# zjb.net
KiCad netlist of a schematic drawn in Altium Designer
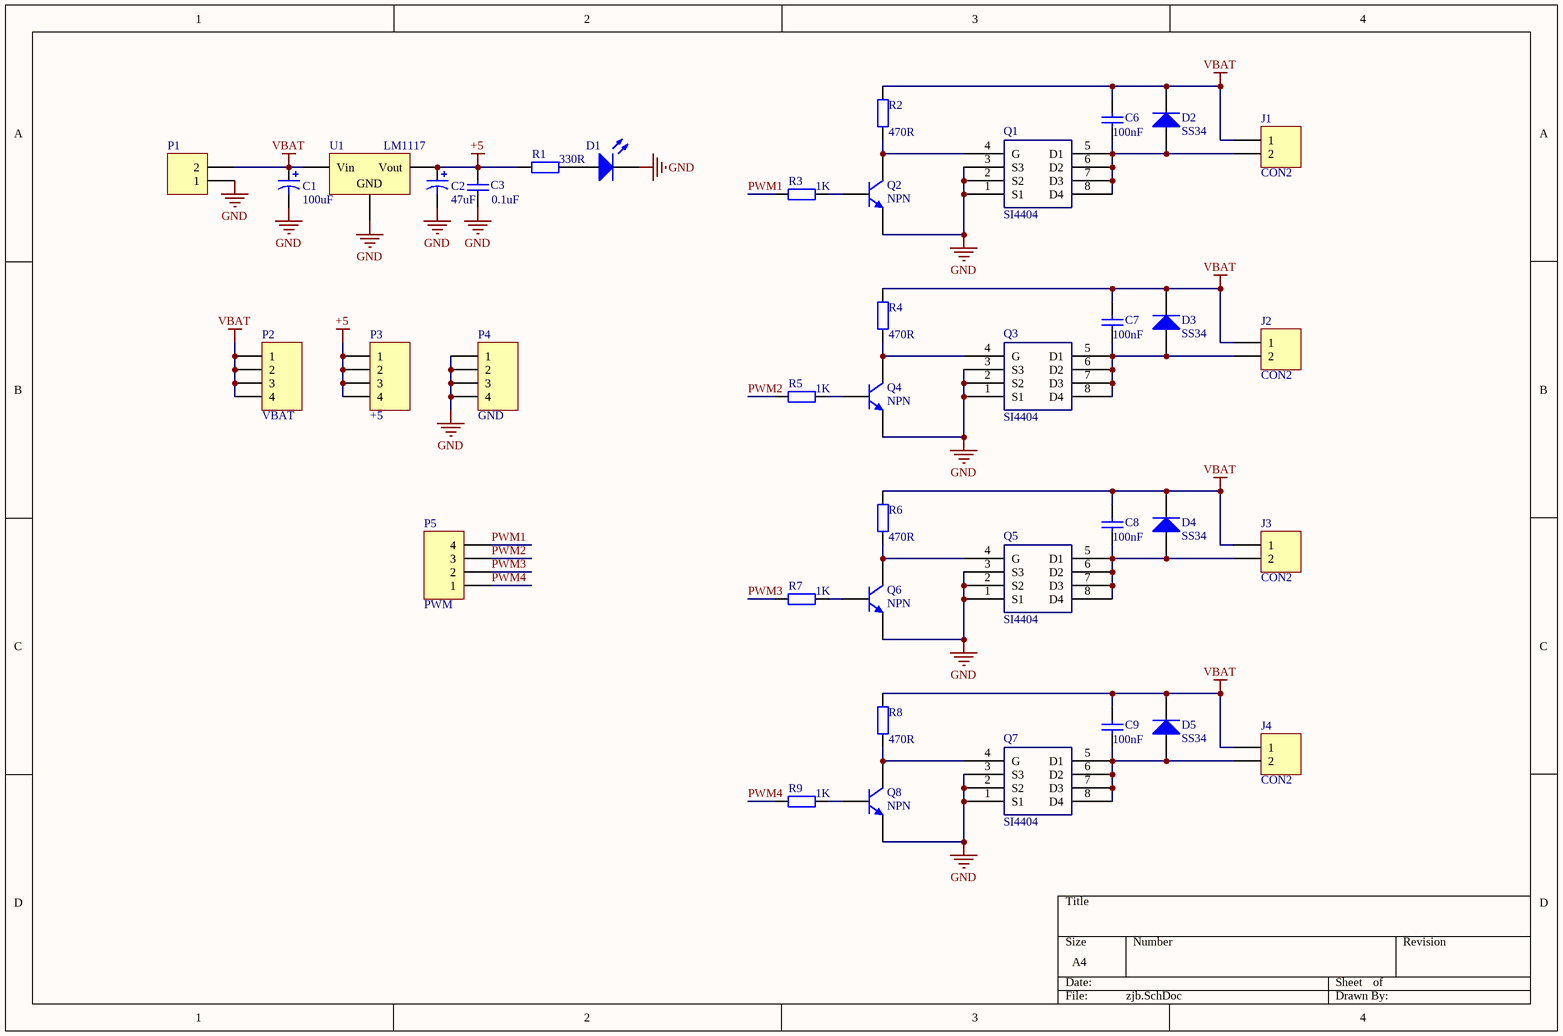
[diagram p0: zjb.SchDoc]

(export (version "E")
  (design (tool "Eeschema 10.0.6"))
  (components
    (comp (ref "C1")
      (value "100uF")
      (footprint "C0805")
      (description "Polarized Capacitor (Surface Mount)")
      (fields (field (name "Comment") "Cap Pol3") (field (name "PUBLISHER") "Altium Limited"))
      (libsource (lib "Miscellaneous Devices") (part "Cap Pol3"))
    )
    (comp (ref "C2")
      (value "47uF")
      (footprint "C0805")
      (description "Polarized Capacitor (Surface Mount)")
      (fields (field (name "Comment") "Cap Pol3") (field (name "PUBLISHER") "Altium Limited"))
      (libsource (lib "Miscellaneous Devices") (part "Cap Pol3"))
    )
    (comp (ref "C3")
      (value "0.1uF")
      (footprint "C0805")
      (description "Capacitor")
      (fields (field (name "Comment") "Cap") (field (name "PUBLISHER") "Altium Limited"))
      (libsource (lib "Miscellaneous Devices") (part "Cap"))
    )
    (comp (ref "C6")
      (value "100nF")
      (footprint "C0805")
      (description "Capacitor")
      (fields (field (name "Comment") "Cap") (field (name "PUBLISHER") "Altium Limited"))
      (libsource (lib "Miscellaneous Devices") (part "Cap"))
    )
    (comp (ref "C7")
      (value "100nF")
      (footprint "C0805")
      (description "Capacitor")
      (fields (field (name "Comment") "Cap") (field (name "PUBLISHER") "Altium Limited"))
      (libsource (lib "Miscellaneous Devices") (part "Cap"))
    )
    (comp (ref "C8")
      (value "100nF")
      (footprint "C0805")
      (description "Capacitor")
      (fields (field (name "Comment") "Cap") (field (name "PUBLISHER") "Altium Limited"))
      (libsource (lib "Miscellaneous Devices") (part "Cap"))
    )
    (comp (ref "C9")
      (value "100nF")
      (footprint "C0805")
      (description "Capacitor")
      (fields (field (name "Comment") "Cap") (field (name "PUBLISHER") "Altium Limited"))
      (libsource (lib "Miscellaneous Devices") (part "Cap"))
    )
    (comp (ref "D1")
      (value "LED1")
      (footprint "6-0805")
      (description "Typical INFRARED GaAs LED")
      (fields (field (name "PUBLISHER") "Altium Limited"))
      (libsource (lib "Miscellaneous Devices") (part "LED0"))
    )
    (comp (ref "D2")
      (value "SS34")
      (footprint "SMB")
      (description "Default Diode")
      (fields (field (name "PUBLISHER") "Altium Limited"))
      (libsource (lib "Miscellaneous Devices") (part "Diode"))
    )
    (comp (ref "D3")
      (value "SS34")
      (footprint "SMB")
      (description "Default Diode")
      (fields (field (name "PUBLISHER") "Altium Limited"))
      (libsource (lib "Miscellaneous Devices") (part "Diode"))
    )
    (comp (ref "D4")
      (value "SS34")
      (footprint "SMB")
      (description "Default Diode")
      (fields (field (name "PUBLISHER") "Altium Limited"))
      (libsource (lib "Miscellaneous Devices") (part "Diode"))
    )
    (comp (ref "D5")
      (value "SS34")
      (footprint "SMB")
      (description "Default Diode")
      (fields (field (name "PUBLISHER") "Altium Limited"))
      (libsource (lib "Miscellaneous Devices") (part "Diode"))
    )
    (comp (ref "J1")
      (value "CON2")
      (footprint "HDR1X2")
      (description "Header, 2-Pin")
      (fields (field (name "PUBLISHER") "Altium Limited"))
      (libsource (lib "Miscellaneous Connectors") (part "Header 2"))
    )
    (comp (ref "J2")
      (value "CON2")
      (footprint "HDR1X2")
      (description "Header, 2-Pin")
      (fields (field (name "PUBLISHER") "Altium Limited"))
      (libsource (lib "Miscellaneous Connectors") (part "Header 2"))
    )
    (comp (ref "J3")
      (value "CON2")
      (footprint "HDR1X2")
      (description "Header, 2-Pin")
      (fields (field (name "PUBLISHER") "Altium Limited"))
      (libsource (lib "Miscellaneous Connectors") (part "Header 2"))
    )
    (comp (ref "J4")
      (value "CON2")
      (footprint "HDR1X2")
      (description "Header, 2-Pin")
      (fields (field (name "PUBLISHER") "Altium Limited"))
      (libsource (lib "Miscellaneous Connectors") (part "Header 2"))
    )
    (comp (ref "P1")
      (value "Header 2")
      (footprint "HDR1X2")
      (description "Header, 2-Pin")
      (fields (field (name "PUBLISHER") "Altium Limited"))
      (libsource (lib "") (part "Header 2_1"))
    )
    (comp (ref "P2")
      (value "VBAT")
      (footprint "HDR1X4")
      (description "Header, 4-Pin")
      (fields (field (name "PUBLISHER") "Altium Limited"))
      (libsource (lib "Miscellaneous Connectors") (part "Header 4"))
    )
    (comp (ref "P3")
      (value "+5")
      (footprint "HDR1X4")
      (description "Header, 4-Pin")
      (fields (field (name "PUBLISHER") "Altium Limited"))
      (libsource (lib "Miscellaneous Connectors") (part "Header 4"))
    )
    (comp (ref "P4")
      (value "GND")
      (footprint "HDR1X4")
      (description "Header, 4-Pin")
      (fields (field (name "PUBLISHER") "Altium Limited"))
      (libsource (lib "Miscellaneous Connectors") (part "Header 4"))
    )
    (comp (ref "P5")
      (value "PWM")
      (footprint "HDR1X4")
      (description "Header, 4-Pin")
      (fields (field (name "PUBLISHER") "Altium Limited"))
      (libsource (lib "") (part "Header 4_1"))
    )
    (comp (ref "Q1") (value "SI4404") (footprint "SO8") (libsource (lib "SI4404") (part "Component_1")))
    (comp (ref "Q2")
      (value "NPN")
      (footprint "SOT-23")
      (description "NPN General Purpose Amplifier")
      (fields (field (name "PUBLISHER") "Altium Limited"))
      (libsource (lib "Miscellaneous Devices") (part "2N3904"))
    )
    (comp (ref "Q3") (value "SI4404") (footprint "SO8") (libsource (lib "SI4404") (part "Component_1")))
    (comp (ref "Q4")
      (value "NPN")
      (footprint "SOT-23")
      (description "NPN General Purpose Amplifier")
      (fields (field (name "PUBLISHER") "Altium Limited"))
      (libsource (lib "Miscellaneous Devices") (part "2N3904"))
    )
    (comp (ref "Q5") (value "SI4404") (footprint "SO8") (libsource (lib "SI4404") (part "Component_1")))
    (comp (ref "Q6")
      (value "NPN")
      (footprint "SOT-23")
      (description "NPN General Purpose Amplifier")
      (fields (field (name "PUBLISHER") "Altium Limited"))
      (libsource (lib "Miscellaneous Devices") (part "2N3904"))
    )
    (comp (ref "Q7") (value "SI4404") (footprint "SO8") (libsource (lib "SI4404") (part "Component_1")))
    (comp (ref "Q8")
      (value "NPN")
      (footprint "SOT-23")
      (description "NPN General Purpose Amplifier")
      (fields (field (name "PUBLISHER") "Altium Limited"))
      (libsource (lib "Miscellaneous Devices") (part "2N3904"))
    )
    (comp (ref "R1")
      (value "330R")
      (footprint "6-0805")
      (description "Resistor")
      (fields (field (name "Comment") "Res2") (field (name "PUBLISHER") "Altium Limited"))
      (libsource (lib "Miscellaneous Devices") (part "Res2"))
    )
    (comp (ref "R2")
      (value "470R")
      (footprint "6-0805")
      (description "Resistor")
      (fields (field (name "Comment") "Res2") (field (name "PUBLISHER") "Altium Limited"))
      (libsource (lib "") (part "Res2_1"))
    )
    (comp (ref "R3")
      (value "1K")
      (footprint "6-0805")
      (description "Resistor")
      (fields (field (name "Comment") "Res2") (field (name "PUBLISHER") "Altium Limited"))
      (libsource (lib "Miscellaneous Devices") (part "Res2"))
    )
    (comp (ref "R4")
      (value "470R")
      (footprint "6-0805")
      (description "Resistor")
      (fields (field (name "Comment") "Res2") (field (name "PUBLISHER") "Altium Limited"))
      (libsource (lib "") (part "Res2_1"))
    )
    (comp (ref "R5")
      (value "1K")
      (footprint "6-0805")
      (description "Resistor")
      (fields (field (name "Comment") "Res2") (field (name "PUBLISHER") "Altium Limited"))
      (libsource (lib "Miscellaneous Devices") (part "Res2"))
    )
    (comp (ref "R6")
      (value "470R")
      (footprint "6-0805")
      (description "Resistor")
      (fields (field (name "Comment") "Res2") (field (name "PUBLISHER") "Altium Limited"))
      (libsource (lib "") (part "Res2_1"))
    )
    (comp (ref "R7")
      (value "1K")
      (footprint "6-0805")
      (description "Resistor")
      (fields (field (name "Comment") "Res2") (field (name "PUBLISHER") "Altium Limited"))
      (libsource (lib "Miscellaneous Devices") (part "Res2"))
    )
    (comp (ref "R8")
      (value "470R")
      (footprint "6-0805")
      (description "Resistor")
      (fields (field (name "Comment") "Res2") (field (name "PUBLISHER") "Altium Limited"))
      (libsource (lib "") (part "Res2_1"))
    )
    (comp (ref "R9")
      (value "1K")
      (footprint "6-0805")
      (description "Resistor")
      (fields (field (name "Comment") "Res2") (field (name "PUBLISHER") "Altium Limited"))
      (libsource (lib "Miscellaneous Devices") (part "Res2"))
    )
    (comp (ref "U1")
      (value "LM1117")
      (footprint "SOT223")
      (description "Voltage Regulator")
      (fields (field (name "PUBLISHER") "Altium Limited"))
      (libsource (lib "Miscellaneous Devices") (part "Volt Reg"))
    )
  )
  (nets
    (net (code "1") (name "+5") (class "Default")
      (node (ref "C2") (pin "1") (pinfunction "1_1") (pintype "passive"))
      (node (ref "C3") (pin "2") (pinfunction "2_2") (pintype "passive"))
      (node (ref "P3") (pin "1") (pinfunction "1_1") (pintype "passive"))
      (node (ref "P3") (pin "2") (pinfunction "2_2") (pintype "passive"))
      (node (ref "P3") (pin "3") (pinfunction "3_3") (pintype "passive"))
      (node (ref "P3") (pin "4") (pinfunction "4_4") (pintype "passive"))
      (node (ref "R1") (pin "1") (pinfunction "1_1") (pintype "passive"))
      (node (ref "U1") (pin "3") (pinfunction "Vout_3") (pintype "passive"))
    )
    (net (code "2") (name "/PWM1") (class "Default")
      (node (ref "P5") (pin "4") (pinfunction "4_4") (pintype "passive"))
      (node (ref "R3") (pin "1") (pinfunction "1_1") (pintype "passive"))
    )
    (net (code "3") (name "/PWM2") (class "Default")
      (node (ref "P5") (pin "3") (pinfunction "3_3") (pintype "passive"))
      (node (ref "R5") (pin "1") (pinfunction "1_1") (pintype "passive"))
    )
    (net (code "4") (name "/PWM3") (class "Default")
      (node (ref "P5") (pin "2") (pinfunction "2_2") (pintype "passive"))
      (node (ref "R7") (pin "1") (pinfunction "1_1") (pintype "passive"))
    )
    (net (code "5") (name "/PWM4") (class "Default")
      (node (ref "P5") (pin "1") (pinfunction "1_1") (pintype "passive"))
      (node (ref "R9") (pin "1") (pinfunction "1_1") (pintype "passive"))
    )
    (net (code "6") (name "GND") (class "Default")
      (node (ref "C1") (pin "2") (pinfunction "2_2") (pintype "passive"))
      (node (ref "C2") (pin "2") (pinfunction "2_2") (pintype "passive"))
      (node (ref "C3") (pin "1") (pinfunction "1_1") (pintype "passive"))
      (node (ref "D1") (pin "2") (pinfunction "K_2") (pintype "passive"))
      (node (ref "P1") (pin "1") (pinfunction "1_1") (pintype "passive"))
      (node (ref "P4") (pin "1") (pinfunction "1_1") (pintype "passive"))
      (node (ref "P4") (pin "2") (pinfunction "2_2") (pintype "passive"))
      (node (ref "P4") (pin "3") (pinfunction "3_3") (pintype "passive"))
      (node (ref "P4") (pin "4") (pinfunction "4_4") (pintype "passive"))
      (node (ref "Q1") (pin "1") (pinfunction "S1_1") (pintype "passive"))
      (node (ref "Q1") (pin "2") (pinfunction "S2_2") (pintype "passive"))
      (node (ref "Q1") (pin "3") (pinfunction "S3_3") (pintype "passive"))
      (node (ref "Q2") (pin "1") (pinfunction "E_1") (pintype "passive"))
      (node (ref "Q3") (pin "1") (pinfunction "S1_1") (pintype "passive"))
      (node (ref "Q3") (pin "2") (pinfunction "S2_2") (pintype "passive"))
      (node (ref "Q3") (pin "3") (pinfunction "S3_3") (pintype "passive"))
      (node (ref "Q4") (pin "1") (pinfunction "E_1") (pintype "passive"))
      (node (ref "Q5") (pin "1") (pinfunction "S1_1") (pintype "passive"))
      (node (ref "Q5") (pin "2") (pinfunction "S2_2") (pintype "passive"))
      (node (ref "Q5") (pin "3") (pinfunction "S3_3") (pintype "passive"))
      (node (ref "Q6") (pin "1") (pinfunction "E_1") (pintype "passive"))
      (node (ref "Q7") (pin "1") (pinfunction "S1_1") (pintype "passive"))
      (node (ref "Q7") (pin "2") (pinfunction "S2_2") (pintype "passive"))
      (node (ref "Q7") (pin "3") (pinfunction "S3_3") (pintype "passive"))
      (node (ref "Q8") (pin "1") (pinfunction "E_1") (pintype "passive"))
      (node (ref "U1") (pin "2") (pinfunction "GND_2") (pintype "passive"))
    )
    (net (code "7") (name "Net-(D1-A)") (class "Default")
      (node (ref "D1") (pin "1") (pinfunction "A_1") (pintype "passive"))
      (node (ref "R1") (pin "2") (pinfunction "2_2") (pintype "passive"))
    )
    (net (code "8") (name "Net-(D2-A)") (class "Default")
      (node (ref "C6") (pin "1") (pinfunction "1_1") (pintype "passive"))
      (node (ref "D2") (pin "1") (pinfunction "A_1") (pintype "passive"))
      (node (ref "J1") (pin "2") (pinfunction "2_2") (pintype "passive"))
      (node (ref "Q1") (pin "5") (pinfunction "D1_5") (pintype "passive"))
      (node (ref "Q1") (pin "6") (pinfunction "D2_6") (pintype "passive"))
      (node (ref "Q1") (pin "7") (pinfunction "D3_7") (pintype "passive"))
      (node (ref "Q1") (pin "8") (pinfunction "D4_8") (pintype "passive"))
    )
    (net (code "9") (name "Net-(D3-A)") (class "Default")
      (node (ref "C7") (pin "1") (pinfunction "1_1") (pintype "passive"))
      (node (ref "D3") (pin "1") (pinfunction "A_1") (pintype "passive"))
      (node (ref "J2") (pin "2") (pinfunction "2_2") (pintype "passive"))
      (node (ref "Q3") (pin "5") (pinfunction "D1_5") (pintype "passive"))
      (node (ref "Q3") (pin "6") (pinfunction "D2_6") (pintype "passive"))
      (node (ref "Q3") (pin "7") (pinfunction "D3_7") (pintype "passive"))
      (node (ref "Q3") (pin "8") (pinfunction "D4_8") (pintype "passive"))
    )
    (net (code "10") (name "Net-(D4-A)") (class "Default")
      (node (ref "C8") (pin "1") (pinfunction "1_1") (pintype "passive"))
      (node (ref "D4") (pin "1") (pinfunction "A_1") (pintype "passive"))
      (node (ref "J3") (pin "2") (pinfunction "2_2") (pintype "passive"))
      (node (ref "Q5") (pin "5") (pinfunction "D1_5") (pintype "passive"))
      (node (ref "Q5") (pin "6") (pinfunction "D2_6") (pintype "passive"))
      (node (ref "Q5") (pin "7") (pinfunction "D3_7") (pintype "passive"))
      (node (ref "Q5") (pin "8") (pinfunction "D4_8") (pintype "passive"))
    )
    (net (code "11") (name "Net-(D5-A)") (class "Default")
      (node (ref "C9") (pin "1") (pinfunction "1_1") (pintype "passive"))
      (node (ref "D5") (pin "1") (pinfunction "A_1") (pintype "passive"))
      (node (ref "J4") (pin "2") (pinfunction "2_2") (pintype "passive"))
      (node (ref "Q7") (pin "5") (pinfunction "D1_5") (pintype "passive"))
      (node (ref "Q7") (pin "6") (pinfunction "D2_6") (pintype "passive"))
      (node (ref "Q7") (pin "7") (pinfunction "D3_7") (pintype "passive"))
      (node (ref "Q7") (pin "8") (pinfunction "D4_8") (pintype "passive"))
    )
    (net (code "12") (name "Net-(Q1-G)") (class "Default")
      (node (ref "Q1") (pin "4") (pinfunction "G_4") (pintype "passive"))
      (node (ref "Q2") (pin "3") (pinfunction "C_3") (pintype "passive"))
      (node (ref "R2") (pin "1") (pinfunction "1_1") (pintype "passive"))
    )
    (net (code "13") (name "Net-(Q2-B)") (class "Default")
      (node (ref "Q2") (pin "2") (pinfunction "B_2") (pintype "passive"))
      (node (ref "R3") (pin "2") (pinfunction "2_2") (pintype "passive"))
    )
    (net (code "14") (name "Net-(Q3-G)") (class "Default")
      (node (ref "Q3") (pin "4") (pinfunction "G_4") (pintype "passive"))
      (node (ref "Q4") (pin "3") (pinfunction "C_3") (pintype "passive"))
      (node (ref "R4") (pin "1") (pinfunction "1_1") (pintype "passive"))
    )
    (net (code "15") (name "Net-(Q4-B)") (class "Default")
      (node (ref "Q4") (pin "2") (pinfunction "B_2") (pintype "passive"))
      (node (ref "R5") (pin "2") (pinfunction "2_2") (pintype "passive"))
    )
    (net (code "16") (name "Net-(Q5-G)") (class "Default")
      (node (ref "Q5") (pin "4") (pinfunction "G_4") (pintype "passive"))
      (node (ref "Q6") (pin "3") (pinfunction "C_3") (pintype "passive"))
      (node (ref "R6") (pin "1") (pinfunction "1_1") (pintype "passive"))
    )
    (net (code "17") (name "Net-(Q6-B)") (class "Default")
      (node (ref "Q6") (pin "2") (pinfunction "B_2") (pintype "passive"))
      (node (ref "R7") (pin "2") (pinfunction "2_2") (pintype "passive"))
    )
    (net (code "18") (name "Net-(Q7-G)") (class "Default")
      (node (ref "Q7") (pin "4") (pinfunction "G_4") (pintype "passive"))
      (node (ref "Q8") (pin "3") (pinfunction "C_3") (pintype "passive"))
      (node (ref "R8") (pin "1") (pinfunction "1_1") (pintype "passive"))
    )
    (net (code "19") (name "Net-(Q8-B)") (class "Default")
      (node (ref "Q8") (pin "2") (pinfunction "B_2") (pintype "passive"))
      (node (ref "R9") (pin "2") (pinfunction "2_2") (pintype "passive"))
    )
    (net (code "20") (name "VBAT") (class "Default")
      (node (ref "C1") (pin "1") (pinfunction "1_1") (pintype "passive"))
      (node (ref "C6") (pin "2") (pinfunction "2_2") (pintype "passive"))
      (node (ref "C7") (pin "2") (pinfunction "2_2") (pintype "passive"))
      (node (ref "C8") (pin "2") (pinfunction "2_2") (pintype "passive"))
      (node (ref "C9") (pin "2") (pinfunction "2_2") (pintype "passive"))
      (node (ref "D2") (pin "2") (pinfunction "K_2") (pintype "passive"))
      (node (ref "D3") (pin "2") (pinfunction "K_2") (pintype "passive"))
      (node (ref "D4") (pin "2") (pinfunction "K_2") (pintype "passive"))
      (node (ref "D5") (pin "2") (pinfunction "K_2") (pintype "passive"))
      (node (ref "J1") (pin "1") (pinfunction "1_1") (pintype "passive"))
      (node (ref "J2") (pin "1") (pinfunction "1_1") (pintype "passive"))
      (node (ref "J3") (pin "1") (pinfunction "1_1") (pintype "passive"))
      (node (ref "J4") (pin "1") (pinfunction "1_1") (pintype "passive"))
      (node (ref "P1") (pin "2") (pinfunction "2_2") (pintype "passive"))
      (node (ref "P2") (pin "1") (pinfunction "1_1") (pintype "passive"))
      (node (ref "P2") (pin "2") (pinfunction "2_2") (pintype "passive"))
      (node (ref "P2") (pin "3") (pinfunction "3_3") (pintype "passive"))
      (node (ref "P2") (pin "4") (pinfunction "4_4") (pintype "passive"))
      (node (ref "R2") (pin "2") (pinfunction "2_2") (pintype "passive"))
      (node (ref "R4") (pin "2") (pinfunction "2_2") (pintype "passive"))
      (node (ref "R6") (pin "2") (pinfunction "2_2") (pintype "passive"))
      (node (ref "R8") (pin "2") (pinfunction "2_2") (pintype "passive"))
      (node (ref "U1") (pin "1") (pinfunction "Vin_1") (pintype "passive"))
    )
  )
)
